# SCC_MPPT_EASYEDA_Schematic.net
KiCad netlist of a schematic drawn in EasyEDA
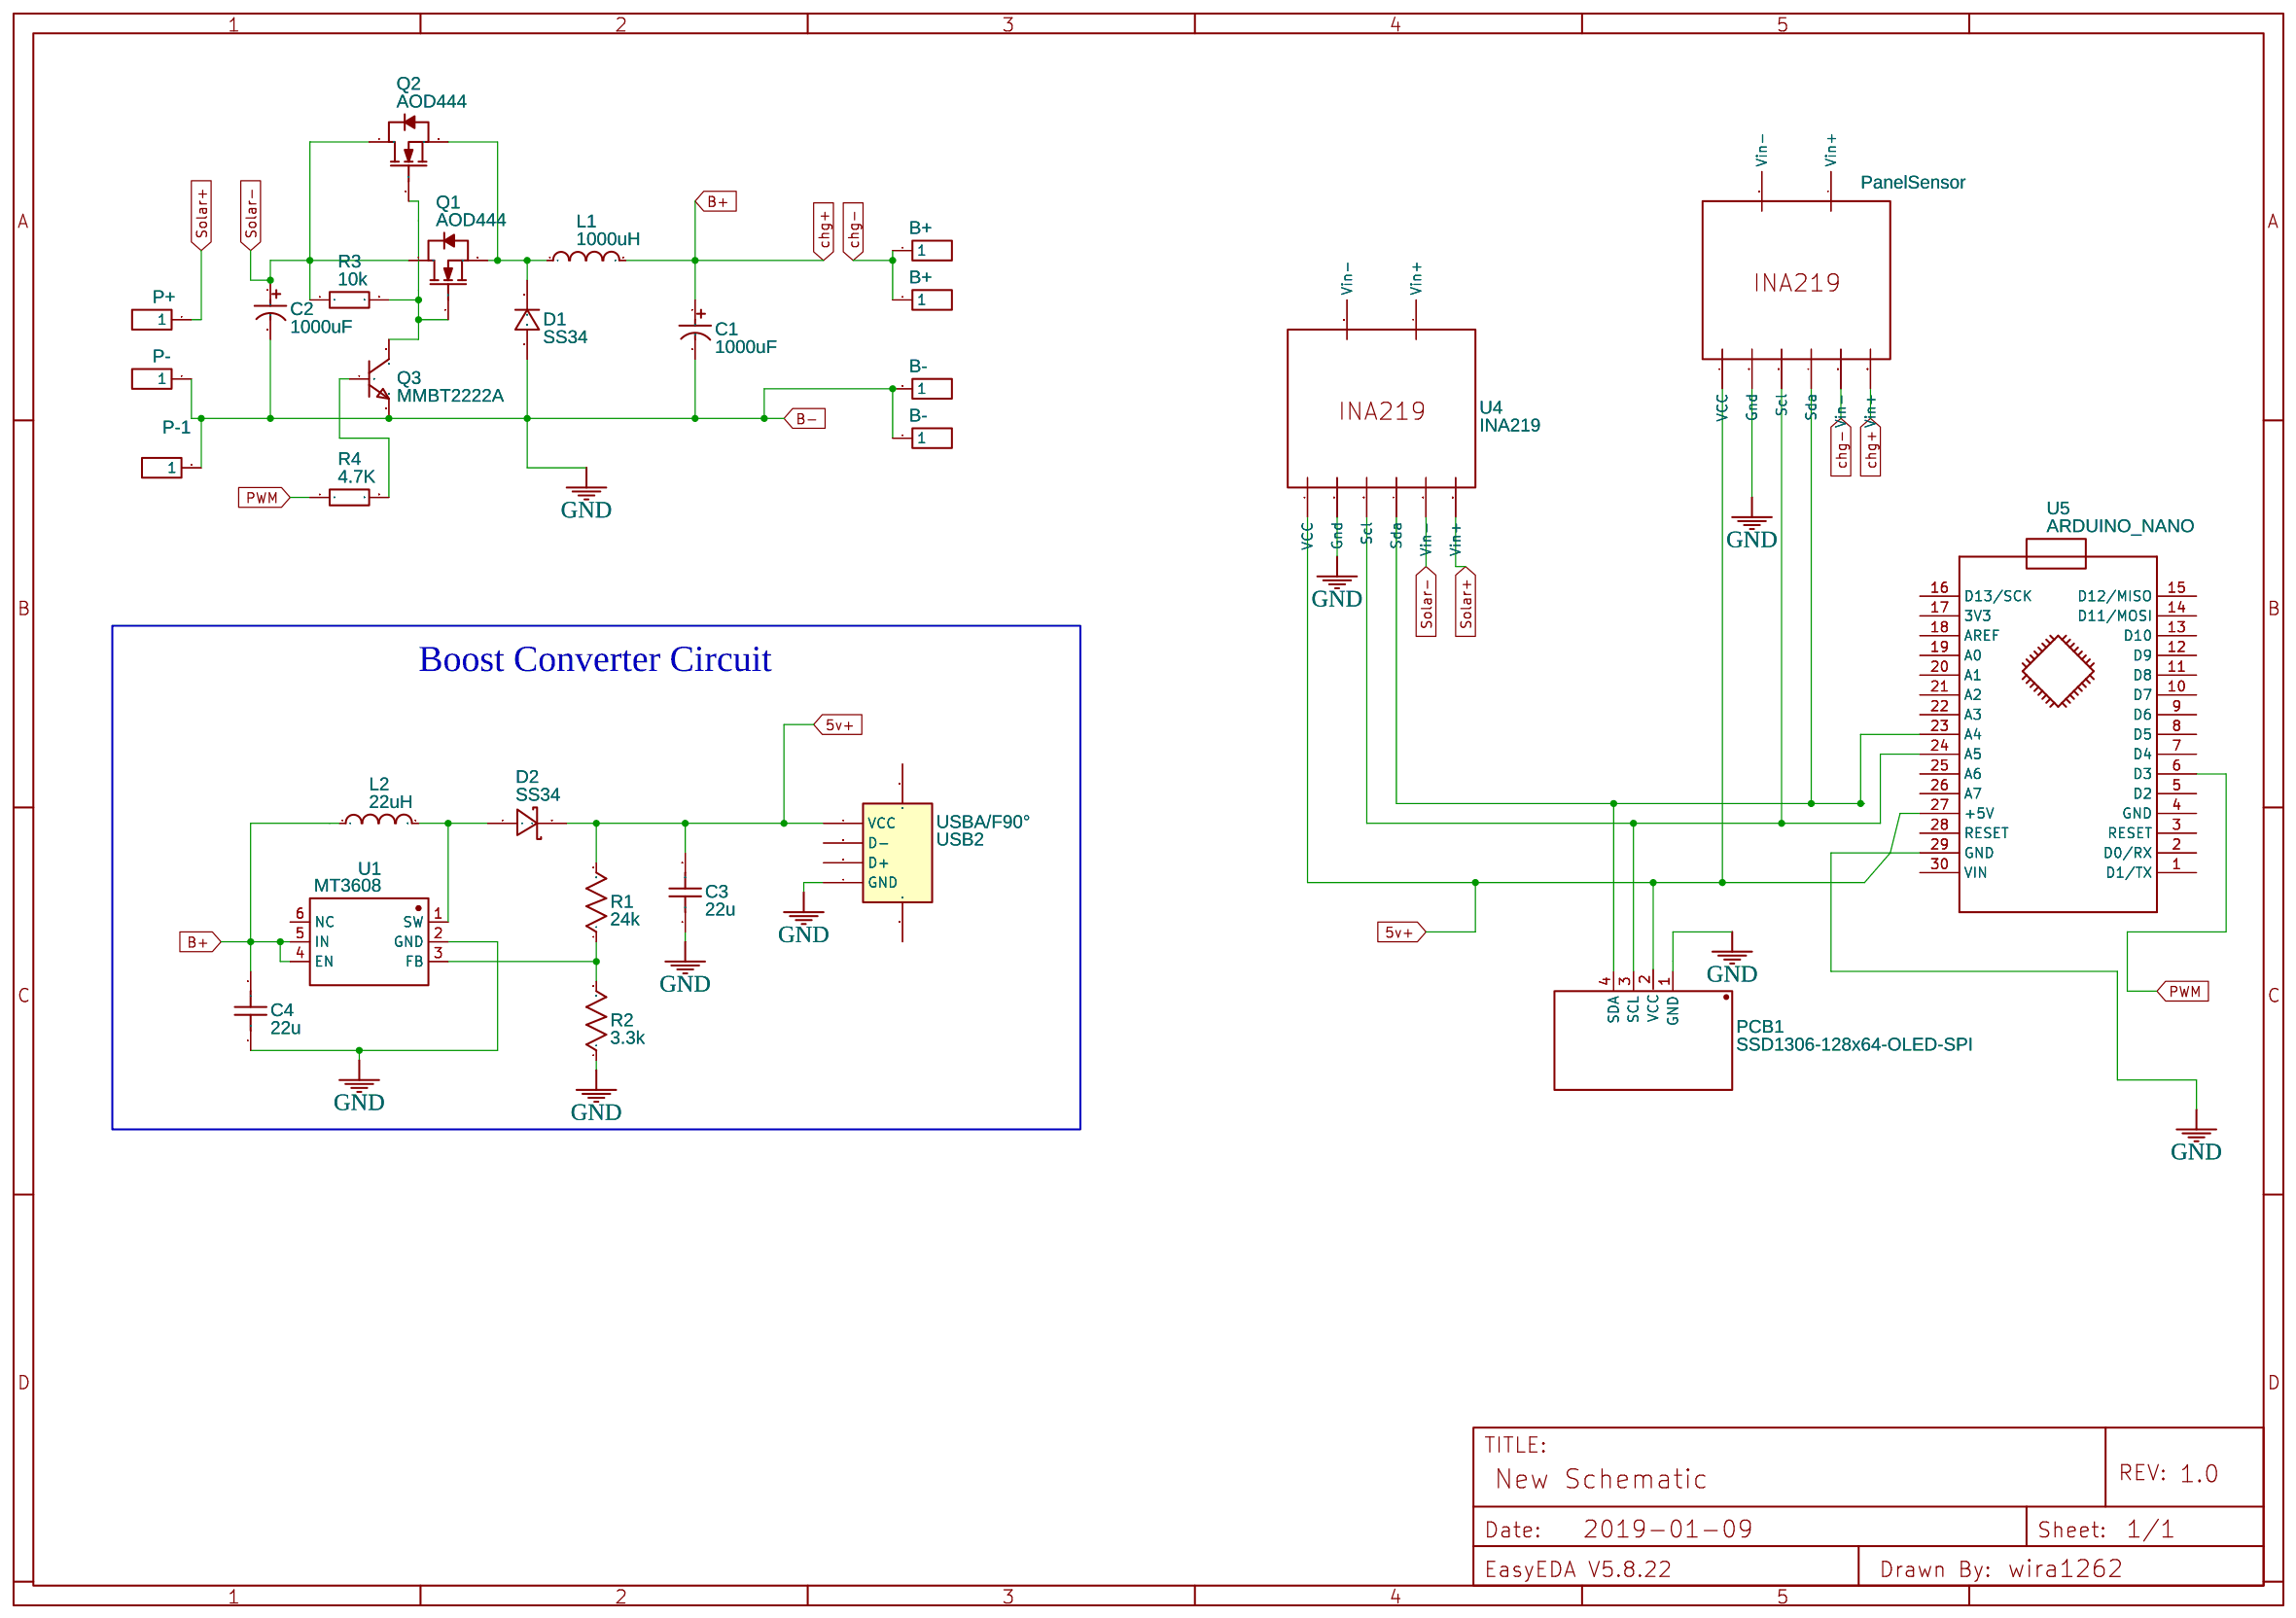
[diagram p0: schematic sheet]

(export (version "E")
  (design (tool "Eeschema 10.0.6"))
  (components
    (comp (ref "B+1")
      (value "B+")
      (fields
        (field (name "BOM_Manufacturer Part") "Header-Male-2.54_1x1")
        (field (name "BOM_Supplier Part") "C81276")
      )
      (libsource (lib "") (part "Unknown_460_120"))
    )
    (comp (ref "B+2")
      (value "B+")
      (fields
        (field (name "BOM_Manufacturer Part") "Header-Male-2.54_1x1")
        (field (name "BOM_Supplier Part") "C81276")
      )
      (libsource (lib "") (part "Unknown_460_145"))
    )
    (comp (ref "B-1")
      (value "B-")
      (fields
        (field (name "BOM_Manufacturer Part") "Header-Male-2.54_1x1")
        (field (name "BOM_Supplier Part") "C81276")
      )
      (libsource (lib "") (part "Unknown_460_190"))
    )
    (comp (ref "B-2")
      (value "B-")
      (fields
        (field (name "BOM_Manufacturer Part") "Header-Male-2.54_1x1")
        (field (name "BOM_Supplier Part") "C81276")
      )
      (libsource (lib "") (part "Unknown_460_215"))
    )
    (comp (ref "C1")
      (value "1000uF")
      (fields (field (name "BOM_Manufacturer Part") "1000uF 25V") (field (name "BOM_Supplier Part") "C10750"))
      (libsource (lib "") (part "1000uF 25V"))
    )
    (comp (ref "C2")
      (value "1000uF")
      (fields (field (name "BOM_Manufacturer Part") "1000uF 25V") (field (name "BOM_Supplier Part") "C10750"))
      (libsource (lib "") (part "1000uF 25V"))
    )
    (comp (ref "C3")
      (value "22u")
      (fields (field (name "BOM_Manufacturer Part") "?"))
      (libsource (lib "") (part "Cap_0805_US"))
    )
    (comp (ref "C4")
      (value "22u")
      (fields (field (name "BOM_Manufacturer Part") "?"))
      (libsource (lib "") (part "Cap_0805_US"))
    )
    (comp (ref "D1")
      (value "SS34")
      (fields (field (name "BOM_Supplier Part") "C169162"))
      (libsource (lib "") (part "Unknown_260_155"))
    )
    (comp (ref "D2")
      (value "SS34")
      (fields (field (name "BOM_Supplier Part") "C8678"))
      (libsource (lib "") (part "Unknown_260_410"))
    )
    (comp (ref "L1")
      (value "1000uH")
      (fields
        (field (name "BOM_Manufacturer Part") "VLU1012-102KB")
        (field (name "BOM_Supplier Part") "C142469")
      )
      (libsource (lib "") (part "VLU1012-102KB"))
    )
    (comp (ref "L2")
      (value "22uH")
      (fields
        (field (name "BOM_Manufacturer Part") "SWRH0704B-220MT")
        (field (name "BOM_Supplier Part") "C127734")
      )
      (libsource (lib "") (part "SWRH0704B-220MT"))
    )
    (comp (ref "P+")
      (value "P+")
      (fields
        (field (name "BOM_Manufacturer Part") "Header-Male-2.54_1x1")
        (field (name "BOM_Supplier Part") "C81276")
      )
      (libsource (lib "") (part "Unknown_75_155"))
    )
    (comp (ref "P-")
      (value "P-")
      (fields
        (field (name "BOM_Manufacturer Part") "Header-Male-2.54_1x1")
        (field (name "BOM_Supplier Part") "C81276")
      )
      (libsource (lib "") (part "Unknown_75_185"))
    )
    (comp (ref "P-1")
      (value "Header-Male-2.54_1x1")
      (fields (field (name "BOM_Supplier Part") "C81276"))
      (libsource (lib "") (part "Unknown_80_230"))
    )
    (comp (ref "PCB1")
      (value "SSD1306-128x64-OLED-SPI")
      (fields (field (name "BOM_Manufacturer Part") "?"))
      (libsource (lib "") (part "Unknown_870_495"))
    )
    (comp (ref "Q1")
      (value "AOD444")
      (fields (field (name "BOM_Supplier Part") "C33216"))
      (libsource (lib "") (part "Unknown_220_135"))
    )
    (comp (ref "Q2")
      (value "AOD444")
      (fields (field (name "BOM_Supplier Part") "C33216"))
      (libsource (lib "") (part "Unknown_200_75"))
    )
    (comp (ref "Q3")
      (value "MMBT2222A")
      (fields (field (name "BOM_Supplier Part") "C171740"))
      (libsource (lib "") (part "Unknown_180_185"))
    )
    (comp (ref "R1")
      (value "24k")
      (fields (field (name "BOM_Manufacturer Part") "?"))
      (libsource (lib "") (part "Res_0603(1/10W)_US"))
    )
    (comp (ref "R2")
      (value "3.3k")
      (fields (field (name "BOM_Manufacturer Part") "?"))
      (libsource (lib "") (part "Res_0603(1/10W)_US"))
    )
    (comp (ref "R3")
      (value "10k")
      (fields
        (field (name "BOM_Manufacturer Part") "PTFR1206B10K0P9")
        (field (name "BOM_Supplier Part") "C351536")
      )
      (libsource (lib "") (part "PTFR1206B10K0P9"))
    )
    (comp (ref "R4")
      (value "4.7K")
      (fields
        (field (name "BOM_Manufacturer Part") "PTFR1206B4K70P9")
        (field (name "BOM_Supplier Part") "C351460")
      )
      (libsource (lib "") (part "PTFR1206B4K70P9"))
    )
    (comp (ref "U1")
      (value "MT3608")
      (fields (field (name "BOM_Supplier Part") "C84817"))
      (libsource (lib "") (part "Unknown_190_450"))
    )
    (comp (ref "U3")
      (value "PanelSensor")
      (fields (field (name "BOM_Manufacturer Part") "INA219"))
      (libsource (lib "") (part "Unknown_905_135"))
    )
    (comp (ref "U4") (value "INA219") (libsource (lib "") (part "Unknown_695_200")))
    (comp (ref "U5")
      (value "ARDUINO_NANO")
      (fields (field (name "BOM_Manufacturer Part") "?"))
      (libsource (lib "") (part "Unknown_1035_360"))
    )
    (comp (ref "USB2")
      (value "USBA/F90°")
      (fields (field (name "BOM_Supplier Part") "C44334"))
      (libsource (lib "") (part "Unknown_450_420"))
    )
  )
  (nets
    (net (code "1") (name "5v+") (class "Default")
      (node (ref "C3") (pin "2") (pinfunction "2_2") (pintype "unspecified"))
      (node (ref "D2") (pin "2") (pinfunction "K_2") (pintype "unspecified"))
      (node (ref "PCB1") (pin "2") (pinfunction "VCC_2") (pintype "input"))
      (node (ref "R1") (pin "2") (pinfunction "2_2") (pintype "unspecified"))
      (node (ref "U3") (pin "1") (pinfunction "VCC_1") (pintype "unspecified"))
      (node (ref "U4") (pin "1") (pinfunction "VCC_1") (pintype "unspecified"))
      (node (ref "U5") (pin "27") (pinfunction "+5V_27") (pintype "unspecified"))
      (node (ref "USB2") (pin "1") (pinfunction "VCC_1") (pintype "input"))
    )
    (net (code "2") (name "B+") (class "Default")
      (node (ref "C1") (pin "1") (pinfunction "1_1") (pintype "input"))
      (node (ref "C4") (pin "2") (pinfunction "2_2") (pintype "unspecified"))
      (node (ref "L1") (pin "2") (pinfunction "2_2") (pintype "unspecified"))
      (node (ref "L2") (pin "1") (pinfunction "1_1") (pintype "unspecified"))
      (node (ref "U1") (pin "4") (pinfunction "EN_4") (pintype "unspecified"))
      (node (ref "U1") (pin "5") (pinfunction "IN_5") (pintype "unspecified"))
      (node (ref "U3") (pin "6") (pinfunction "Vin+_6") (pintype "unspecified"))
    )
    (net (code "3") (name "B-") (class "Default")
      (node (ref "B-1") (pin "1") (pinfunction "1_1") (pintype "input"))
      (node (ref "B-2") (pin "1") (pinfunction "1_1") (pintype "input"))
      (node (ref "C1") (pin "2") (pinfunction "2_2") (pintype "input"))
      (node (ref "C2") (pin "2") (pinfunction "2_2") (pintype "input"))
      (node (ref "C3") (pin "1") (pinfunction "1_1") (pintype "unspecified"))
      (node (ref "C4") (pin "1") (pinfunction "1_1") (pintype "unspecified"))
      (node (ref "D1") (pin "1") (pinfunction "1_1") (pintype "unspecified"))
      (node (ref "P-") (pin "1") (pinfunction "1_1") (pintype "input"))
      (node (ref "P-1") (pin "1") (pinfunction "1_1") (pintype "input"))
      (node (ref "PCB1") (pin "1") (pinfunction "GND_1") (pintype "input"))
      (node (ref "Q3") (pin "2") (pinfunction "E_2") (pintype "unspecified"))
      (node (ref "R2") (pin "1") (pinfunction "1_1") (pintype "unspecified"))
      (node (ref "U1") (pin "2") (pinfunction "GND_2") (pintype "unspecified"))
      (node (ref "U3") (pin "2") (pinfunction "Gnd_2") (pintype "unspecified"))
      (node (ref "U4") (pin "2") (pinfunction "Gnd_2") (pintype "unspecified"))
      (node (ref "U5") (pin "29") (pinfunction "GND_29") (pintype "unspecified"))
      (node (ref "USB2") (pin "4") (pinfunction "GND_4") (pintype "input"))
    )
    (net (code "4") (name "Net-(D2-A)") (class "Default")
      (node (ref "D2") (pin "1") (pinfunction "A_1") (pintype "unspecified"))
      (node (ref "L2") (pin "2") (pinfunction "2_2") (pintype "unspecified"))
      (node (ref "U1") (pin "1") (pinfunction "SW_1") (pintype "unspecified"))
    )
    (net (code "5") (name "Net-(PCB1-SCL)") (class "Default")
      (node (ref "PCB1") (pin "3") (pinfunction "SCL_3") (pintype "passive"))
      (node (ref "U3") (pin "3") (pinfunction "Scl_3") (pintype "unspecified"))
      (node (ref "U4") (pin "3") (pinfunction "Scl_3") (pintype "unspecified"))
      (node (ref "U5") (pin "24") (pinfunction "A5_24") (pintype "unspecified"))
    )
    (net (code "6") (name "Net-(PCB1-SDA)") (class "Default")
      (node (ref "PCB1") (pin "4") (pinfunction "SDA_4") (pintype "passive"))
      (node (ref "U3") (pin "4") (pinfunction "Sda_4") (pintype "unspecified"))
      (node (ref "U4") (pin "4") (pinfunction "Sda_4") (pintype "unspecified"))
      (node (ref "U5") (pin "23") (pinfunction "A4_23") (pintype "unspecified"))
    )
    (net (code "7") (name "Net-(Q1-G)") (class "Default")
      (node (ref "Q1") (pin "1") (pinfunction "G_1") (pintype "unspecified"))
      (node (ref "Q2") (pin "1") (pinfunction "G_1") (pintype "unspecified"))
      (node (ref "Q3") (pin "3") (pinfunction "C_3") (pintype "unspecified"))
      (node (ref "R3") (pin "2") (pinfunction "2_2") (pintype "unspecified"))
    )
    (net (code "8") (name "Net-(Q1-S)") (class "Default")
      (node (ref "D1") (pin "2") (pinfunction "2_2") (pintype "unspecified"))
      (node (ref "L1") (pin "1") (pinfunction "1_1") (pintype "unspecified"))
      (node (ref "Q1") (pin "3") (pinfunction "S_3") (pintype "unspecified"))
      (node (ref "Q2") (pin "3") (pinfunction "S_3") (pintype "unspecified"))
    )
    (net (code "9") (name "Net-(Q3-B)") (class "Default")
      (node (ref "Q3") (pin "1") (pinfunction "B_1") (pintype "unspecified"))
      (node (ref "R4") (pin "2") (pinfunction "2_2") (pintype "unspecified"))
    )
    (net (code "10") (name "Net-(U1-FB)") (class "Default")
      (node (ref "R1") (pin "1") (pinfunction "1_1") (pintype "unspecified"))
      (node (ref "R2") (pin "2") (pinfunction "2_2") (pintype "unspecified"))
      (node (ref "U1") (pin "3") (pinfunction "FB_3") (pintype "unspecified"))
    )
    (net (code "11") (name "PWM") (class "Default")
      (node (ref "R4") (pin "1") (pinfunction "1_1") (pintype "unspecified"))
      (node (ref "U5") (pin "6") (pinfunction "D3_6") (pintype "unspecified"))
    )
    (net (code "12") (name "Solar+") (class "Default")
      (node (ref "P+") (pin "1") (pinfunction "1_1") (pintype "input"))
      (node (ref "U4") (pin "6") (pinfunction "Vin+_6") (pintype "unspecified"))
    )
    (net (code "13") (name "Solar-") (class "Default")
      (node (ref "C2") (pin "1") (pinfunction "1_1") (pintype "input"))
      (node (ref "Q1") (pin "4") (pinfunction "D_4") (pintype "unspecified"))
      (node (ref "Q2") (pin "4") (pinfunction "D_4") (pintype "unspecified"))
      (node (ref "R3") (pin "1") (pinfunction "1_1") (pintype "unspecified"))
      (node (ref "U4") (pin "5") (pinfunction "Vin-_5") (pintype "unspecified"))
    )
    (net (code "14") (name "chg-") (class "Default")
      (node (ref "B+1") (pin "1") (pinfunction "1_1") (pintype "input"))
      (node (ref "B+2") (pin "1") (pinfunction "1_1") (pintype "input"))
      (node (ref "U3") (pin "5") (pinfunction "Vin-_5") (pintype "unspecified"))
    )
    (net (code "15") (name "unconnected-(U1-NC-Pad6)") (class "Default")
      (node (ref "U1") (pin "6") (pinfunction "NC_6") (pintype "unspecified"))
    )
    (net (code "16") (name "unconnected-(U3-Vin+-Pad7)") (class "Default")
      (node (ref "U3") (pin "7") (pinfunction "Vin+_7") (pintype "unspecified"))
    )
    (net (code "17") (name "unconnected-(U3-Vin--Pad8)") (class "Default")
      (node (ref "U3") (pin "8") (pinfunction "Vin-_8") (pintype "unspecified"))
    )
    (net (code "18") (name "unconnected-(U4-Vin+-Pad7)") (class "Default")
      (node (ref "U4") (pin "7") (pinfunction "Vin+_7") (pintype "unspecified"))
    )
    (net (code "19") (name "unconnected-(U4-Vin--Pad8)") (class "Default")
      (node (ref "U4") (pin "8") (pinfunction "Vin-_8") (pintype "unspecified"))
    )
    (net (code "20") (name "unconnected-(U5-3V3-Pad17)") (class "Default")
      (node (ref "U5") (pin "17") (pinfunction "3V3_17") (pintype "unspecified"))
    )
    (net (code "21") (name "unconnected-(U5-A0-Pad19)") (class "Default")
      (node (ref "U5") (pin "19") (pinfunction "A0_19") (pintype "unspecified"))
    )
    (net (code "22") (name "unconnected-(U5-A1-Pad20)") (class "Default")
      (node (ref "U5") (pin "20") (pinfunction "A1_20") (pintype "unspecified"))
    )
    (net (code "23") (name "unconnected-(U5-A2-Pad21)") (class "Default")
      (node (ref "U5") (pin "21") (pinfunction "A2_21") (pintype "unspecified"))
    )
    (net (code "24") (name "unconnected-(U5-A3-Pad22)") (class "Default")
      (node (ref "U5") (pin "22") (pinfunction "A3_22") (pintype "unspecified"))
    )
    (net (code "25") (name "unconnected-(U5-A6-Pad25)") (class "Default")
      (node (ref "U5") (pin "25") (pinfunction "A6_25") (pintype "unspecified"))
    )
    (net (code "26") (name "unconnected-(U5-A7-Pad26)") (class "Default")
      (node (ref "U5") (pin "26") (pinfunction "A7_26") (pintype "unspecified"))
    )
    (net (code "27") (name "unconnected-(U5-AREF-Pad18)") (class "Default")
      (node (ref "U5") (pin "18") (pinfunction "AREF_18") (pintype "unspecified"))
    )
    (net (code "28") (name "unconnected-(U5-D0{slash}RX-Pad2)") (class "Default")
      (node (ref "U5") (pin "2") (pinfunction "D0/RX_2") (pintype "unspecified"))
    )
    (net (code "29") (name "unconnected-(U5-D1{slash}TX-Pad1)") (class "Default")
      (node (ref "U5") (pin "1") (pinfunction "D1/TX_1") (pintype "unspecified"))
    )
    (net (code "30") (name "unconnected-(U5-D2-Pad5)") (class "Default")
      (node (ref "U5") (pin "5") (pinfunction "D2_5") (pintype "unspecified"))
    )
    (net (code "31") (name "unconnected-(U5-D4-Pad7)") (class "Default")
      (node (ref "U5") (pin "7") (pinfunction "D4_7") (pintype "unspecified"))
    )
    (net (code "32") (name "unconnected-(U5-D5-Pad8)") (class "Default")
      (node (ref "U5") (pin "8") (pinfunction "D5_8") (pintype "unspecified"))
    )
    (net (code "33") (name "unconnected-(U5-D6-Pad9)") (class "Default")
      (node (ref "U5") (pin "9") (pinfunction "D6_9") (pintype "unspecified"))
    )
    (net (code "34") (name "unconnected-(U5-D7-Pad10)") (class "Default")
      (node (ref "U5") (pin "10") (pinfunction "D7_10") (pintype "unspecified"))
    )
    (net (code "35") (name "unconnected-(U5-D8-Pad11)") (class "Default")
      (node (ref "U5") (pin "11") (pinfunction "D8_11") (pintype "unspecified"))
    )
    (net (code "36") (name "unconnected-(U5-D9-Pad12)") (class "Default")
      (node (ref "U5") (pin "12") (pinfunction "D9_12") (pintype "unspecified"))
    )
    (net (code "37") (name "unconnected-(U5-D10-Pad13)") (class "Default")
      (node (ref "U5") (pin "13") (pinfunction "D10_13") (pintype "unspecified"))
    )
    (net (code "38") (name "unconnected-(U5-D11{slash}MOSI-Pad14)") (class "Default")
      (node (ref "U5") (pin "14") (pinfunction "D11/MOSI_14") (pintype "unspecified"))
    )
    (net (code "39") (name "unconnected-(U5-D12{slash}MISO-Pad15)") (class "Default")
      (node (ref "U5") (pin "15") (pinfunction "D12/MISO_15") (pintype "unspecified"))
    )
    (net (code "40") (name "unconnected-(U5-D13{slash}SCK-Pad16)") (class "Default")
      (node (ref "U5") (pin "16") (pinfunction "D13/SCK_16") (pintype "unspecified"))
    )
    (net (code "41") (name "unconnected-(U5-GND-Pad4)") (class "Default")
      (node (ref "U5") (pin "4") (pinfunction "GND_4") (pintype "unspecified"))
    )
    (net (code "42") (name "unconnected-(U5-RESET-Pad3)") (class "Default")
      (node (ref "U5") (pin "3") (pinfunction "RESET_3") (pintype "unspecified"))
    )
    (net (code "43") (name "unconnected-(U5-RESET-Pad28)") (class "Default")
      (node (ref "U5") (pin "28") (pinfunction "RESET_28") (pintype "unspecified"))
    )
    (net (code "44") (name "unconnected-(U5-VIN-Pad30)") (class "Default")
      (node (ref "U5") (pin "30") (pinfunction "VIN_30") (pintype "unspecified"))
    )
    (net (code "45") (name "unconnected-(USB2-D+-Pad3)") (class "Default")
      (node (ref "USB2") (pin "3") (pinfunction "D+_3") (pintype "input"))
    )
    (net (code "46") (name "unconnected-(USB2-D--Pad2)") (class "Default")
      (node (ref "USB2") (pin "2") (pinfunction "D-_2") (pintype "input"))
    )
    (net (code "47") (name "unconnected-(USB2-Pad0)") (class "Default")
      (node (ref "USB2") (pin "0") (pinfunction "0_0") (pintype "unspecified"))
    )
    (net (code "48") (name "unconnected-(USB2-Pad0)_1") (class "Default")
      (node (ref "USB2") (pin "0") (pinfunction "0_0") (pintype "unspecified"))
    )
  )
)
